# ProtectCircuit.net
KiCad netlist of a schematic drawn in Altium Designer
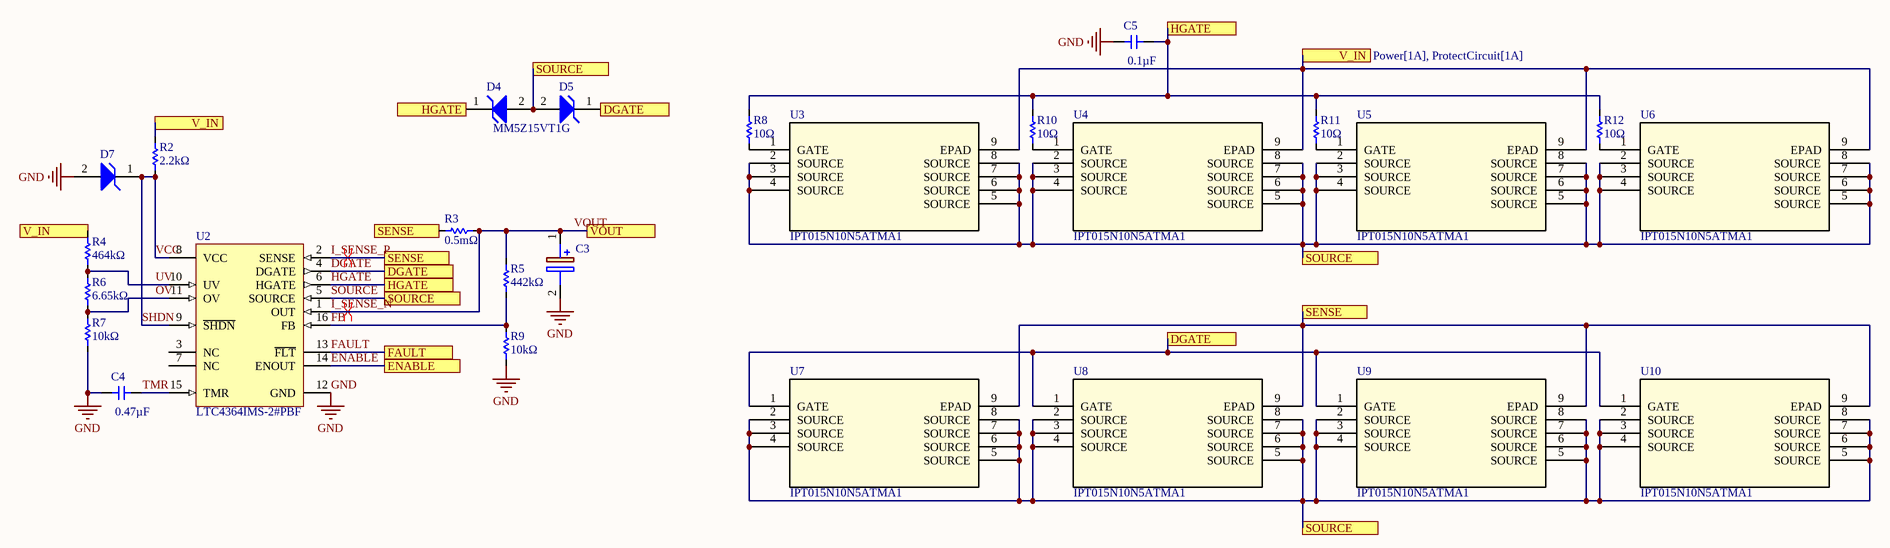
[diagram p0: ProtectCircuit.SchDoc]

(export (version "E")
  (design (tool "Eeschema 10.0.6"))
  (components
    (comp (ref "C3")
      (value "B41858C9477M000")
      (footprint "SamacSys:CAPPRD750W90D1800H3700")
      (description "Capacitor Polarised")
      (fields (field (name "MOUSER PART NUMBER") "871-B41858C9477M"))
      (libsource (lib "*") (part "B41858C9477M000"))
    )
    (comp (ref "C4")
      (value "non-polar_Capacitor")
      (footprint "1210")
      (description "SMD type ceramic capacitor")
      (fields
        (field (name "VOLTAGE") "50V")
        (field (name "CAPACITANCE") "0.47µF")
        (field (name "SOURCE") "robit_passive.SchLib")
      )
      (libsource (lib "robit circuit") (part "Capacitor"))
    )
    (comp (ref "C5")
      (value "non-polar_Capacitor")
      (footprint "1210")
      (description "SMD type ceramic capacitor")
      (fields
        (field (name "VOLTAGE") "50V")
        (field (name "CAPACITANCE") "0.1µF")
        (field (name "SOURCE") "robit_passive.SchLib")
      )
      (libsource (lib "robit circuit") (part "Capacitor"))
    )
    (comp (ref "D4")
      (value "MM5Z15VT1G")
      (footprint "ONSC-SOD-523-2-502-01_V")
      (description "Zener Voltage Regulator, 500 mW, 2-Pin SOD-523, Pb-Free, Tape and Reel")
      (fields (field (name "MANUFACTURER") "On Semiconductor"))
      (libsource (lib "Altium Content Vault") (part "ONSC-K1A2-2"))
    )
    (comp (ref "D5")
      (value "MM5Z15VT1G")
      (footprint "ONSC-SOD-523-2-502-01_V")
      (description "Zener Voltage Regulator, 500 mW, 2-Pin SOD-523, Pb-Free, Tape and Reel")
      (fields (field (name "MANUFACTURER") "On Semiconductor"))
      (libsource (lib "Altium Content Vault") (part "ONSC-K1A2-2"))
    )
    (comp (ref "D7")
      (value "1SMB5945BT3G")
      (footprint "ONSC-SMB-2-403A-03_H_V")
      (description "3 W Zener Voltage Regulator, 2-Pin SMB, Pb-Free, Tape and Reel")
      (fields (field (name "MANUFACTURER") "On Semiconductor"))
      (libsource (lib "Altium Content Vault") (part "ONSC-K1A2-2"))
    )
    (comp (ref "R2") (value "2.2kΩ") (footprint "SMD_2512") (libsource (lib "Resistor") (part "Resistor")))
    (comp (ref "R3") (value "0.5mΩ") (footprint "SMD_2512") (libsource (lib "Resistor") (part "Resistor")))
    (comp (ref "R4") (value "464kΩ") (footprint "SMD_0603") (libsource (lib "Resistor") (part "Resistor")))
    (comp (ref "R5") (value "442kΩ") (footprint "SMD_0603") (libsource (lib "Resistor") (part "Resistor")))
    (comp (ref "R6") (value "6.65kΩ") (footprint "SMD_0603") (libsource (lib "Resistor") (part "Resistor")))
    (comp (ref "R7") (value "10kΩ") (footprint "SMD_0603") (libsource (lib "Resistor") (part "Resistor")))
    (comp (ref "R8") (value "10Ω") (footprint "SMD_0603") (libsource (lib "Resistor") (part "Resistor")))
    (comp (ref "R9") (value "10kΩ") (footprint "SMD_0603") (libsource (lib "Resistor") (part "Resistor")))
    (comp (ref "R10") (value "10Ω") (footprint "SMD_0603") (libsource (lib "Resistor") (part "Resistor")))
    (comp (ref "R11") (value "10Ω") (footprint "SMD_0603") (libsource (lib "Resistor") (part "Resistor")))
    (comp (ref "R12") (value "10Ω") (footprint "SMD_0603") (libsource (lib "Resistor") (part "Resistor")))
    (comp (ref "U2")
      (value "LTC4364IMS-2#PBF")
      (footprint "LT-MS-16_M")
      (description "Surge Stopper with Ideal Diode, 4 to 80 V Vin, 16-pin SOP (MS-16), -40 to 85 degC, Pb-Free")
      (fields (field (name "MANUFACTURER") "Linear Technology"))
      (libsource (lib "Altium Content Vault") (part "LT-LTC4364-S-16"))
    )
    (comp (ref "U3")
      (value "IPT015N10N5ATMA1")
      (footprint "PG-HSOF-8-1_INF")
      (fields (field (name "COPYRIGHT") "Copyright (C) 2025 Ultra Librarian. All rights reserved."))
      (libsource (lib "IPT015N10N5ATMA1") (part "IPT015N10N5ATMA1"))
    )
    (comp (ref "U4")
      (value "IPT015N10N5ATMA1")
      (footprint "PG-HSOF-8-1_INF")
      (fields (field (name "COPYRIGHT") "Copyright (C) 2025 Ultra Librarian. All rights reserved."))
      (libsource (lib "IPT015N10N5ATMA1") (part "IPT015N10N5ATMA1"))
    )
    (comp (ref "U5")
      (value "IPT015N10N5ATMA1")
      (footprint "PG-HSOF-8-1_INF")
      (fields (field (name "COPYRIGHT") "Copyright (C) 2025 Ultra Librarian. All rights reserved."))
      (libsource (lib "IPT015N10N5ATMA1") (part "IPT015N10N5ATMA1"))
    )
    (comp (ref "U6")
      (value "IPT015N10N5ATMA1")
      (footprint "PG-HSOF-8-1_INF")
      (fields (field (name "COPYRIGHT") "Copyright (C) 2025 Ultra Librarian. All rights reserved."))
      (libsource (lib "IPT015N10N5ATMA1") (part "IPT015N10N5ATMA1"))
    )
    (comp (ref "U7")
      (value "IPT015N10N5ATMA1")
      (footprint "PG-HSOF-8-1_INF")
      (fields (field (name "COPYRIGHT") "Copyright (C) 2025 Ultra Librarian. All rights reserved."))
      (libsource (lib "IPT015N10N5ATMA1") (part "IPT015N10N5ATMA1"))
    )
    (comp (ref "U8")
      (value "IPT015N10N5ATMA1")
      (footprint "PG-HSOF-8-1_INF")
      (fields (field (name "COPYRIGHT") "Copyright (C) 2025 Ultra Librarian. All rights reserved."))
      (libsource (lib "IPT015N10N5ATMA1") (part "IPT015N10N5ATMA1"))
    )
    (comp (ref "U9")
      (value "IPT015N10N5ATMA1")
      (footprint "PG-HSOF-8-1_INF")
      (fields (field (name "COPYRIGHT") "Copyright (C) 2025 Ultra Librarian. All rights reserved."))
      (libsource (lib "IPT015N10N5ATMA1") (part "IPT015N10N5ATMA1"))
    )
    (comp (ref "U10")
      (value "IPT015N10N5ATMA1")
      (footprint "PG-HSOF-8-1_INF")
      (fields (field (name "COPYRIGHT") "Copyright (C) 2025 Ultra Librarian. All rights reserved."))
      (libsource (lib "IPT015N10N5ATMA1") (part "IPT015N10N5ATMA1"))
    )
  )
  (nets
    (net (code "1") (name "/DGATE") (class "Default")
      (node (ref "D5") (pin "1") (pinfunction "K_1") (pintype "passive"))
      (node (ref "U10") (pin "1") (pinfunction "GATE_1") (pintype "passive"))
      (node (ref "U2") (pin "4") (pinfunction "DGATE_4") (pintype "output"))
      (node (ref "U7") (pin "1") (pinfunction "GATE_1") (pintype "passive"))
      (node (ref "U8") (pin "1") (pinfunction "GATE_1") (pintype "passive"))
      (node (ref "U9") (pin "1") (pinfunction "GATE_1") (pintype "passive"))
    )
    (net (code "2") (name "/ENABLE") (class "Default")
      (node (ref "U2") (pin "14") (pinfunction "ENOUT_14") (pintype "tri_state"))
    )
    (net (code "3") (name "/FAULT") (class "Default")
      (node (ref "U2") (pin "13") (pinfunction "~{FLT}_13") (pintype "tri_state"))
    )
    (net (code "4") (name "/FB") (class "Default")
      (node (ref "R5") (pin "2") (pinfunction "2_2") (pintype "passive"))
      (node (ref "R9") (pin "1") (pinfunction "1_1") (pintype "passive"))
      (node (ref "U2") (pin "16") (pinfunction "FB_16") (pintype "input"))
    )
    (net (code "5") (name "/HGATE") (class "Default")
      (node (ref "C5") (pin "2") (pinfunction "2_2") (pintype "passive"))
      (node (ref "D4") (pin "1") (pinfunction "K_1") (pintype "passive"))
      (node (ref "R10") (pin "1") (pinfunction "1_1") (pintype "passive"))
      (node (ref "R11") (pin "1") (pinfunction "1_1") (pintype "passive"))
      (node (ref "R12") (pin "1") (pinfunction "1_1") (pintype "passive"))
      (node (ref "R8") (pin "1") (pinfunction "1_1") (pintype "passive"))
      (node (ref "U2") (pin "6") (pinfunction "HGATE_6") (pintype "output"))
    )
    (net (code "6") (name "/I_SENSE_N") (class "Default")
      (node (ref "C3") (pin "1") (pinfunction "+_1") (pintype "passive"))
      (node (ref "R3") (pin "2") (pinfunction "2_2") (pintype "passive"))
      (node (ref "R5") (pin "1") (pinfunction "1_1") (pintype "passive"))
      (node (ref "U2") (pin "1") (pinfunction "OUT_1") (pintype "input"))
    )
    (net (code "7") (name "/I_SENSE_P") (class "Default")
      (node (ref "R3") (pin "1") (pinfunction "1_1") (pintype "passive"))
      (node (ref "U10") (pin "9") (pinfunction "EPAD_9") (pintype "passive"))
      (node (ref "U2") (pin "2") (pinfunction "SENSE_2") (pintype "input"))
      (node (ref "U7") (pin "9") (pinfunction "EPAD_9") (pintype "passive"))
      (node (ref "U8") (pin "9") (pinfunction "EPAD_9") (pintype "passive"))
      (node (ref "U9") (pin "9") (pinfunction "EPAD_9") (pintype "passive"))
    )
    (net (code "8") (name "/OV") (class "Default")
      (node (ref "R6") (pin "2") (pinfunction "2_2") (pintype "passive"))
      (node (ref "R7") (pin "1") (pinfunction "1_1") (pintype "passive"))
      (node (ref "U2") (pin "11") (pinfunction "OV_11") (pintype "input"))
    )
    (net (code "9") (name "/SHDN") (class "Default")
      (node (ref "D7") (pin "1") (pinfunction "K_1") (pintype "passive"))
      (node (ref "R2") (pin "2") (pinfunction "2_2") (pintype "passive"))
      (node (ref "U2") (pin "8") (pinfunction "VCC_8") (pintype "power_in"))
      (node (ref "U2") (pin "9") (pinfunction "~{SHDN}_9") (pintype "input"))
    )
    (net (code "10") (name "/SOURCE") (class "Default")
      (node (ref "D4") (pin "2") (pinfunction "A_2") (pintype "passive"))
      (node (ref "D5") (pin "2") (pinfunction "A_2") (pintype "passive"))
      (node (ref "U10") (pin "2") (pinfunction "SOURCE_2") (pintype "passive"))
      (node (ref "U10") (pin "3") (pinfunction "SOURCE_3") (pintype "passive"))
      (node (ref "U10") (pin "4") (pinfunction "SOURCE_4") (pintype "passive"))
      (node (ref "U10") (pin "5") (pinfunction "SOURCE_5") (pintype "passive"))
      (node (ref "U10") (pin "6") (pinfunction "SOURCE_6") (pintype "passive"))
      (node (ref "U10") (pin "7") (pinfunction "SOURCE_7") (pintype "passive"))
      (node (ref "U10") (pin "8") (pinfunction "SOURCE_8") (pintype "passive"))
      (node (ref "U2") (pin "5") (pinfunction "SOURCE_5") (pintype "input"))
      (node (ref "U3") (pin "2") (pinfunction "SOURCE_2") (pintype "passive"))
      (node (ref "U3") (pin "3") (pinfunction "SOURCE_3") (pintype "passive"))
      (node (ref "U3") (pin "4") (pinfunction "SOURCE_4") (pintype "passive"))
      (node (ref "U3") (pin "5") (pinfunction "SOURCE_5") (pintype "passive"))
      (node (ref "U3") (pin "6") (pinfunction "SOURCE_6") (pintype "passive"))
      (node (ref "U3") (pin "7") (pinfunction "SOURCE_7") (pintype "passive"))
      (node (ref "U3") (pin "8") (pinfunction "SOURCE_8") (pintype "passive"))
      (node (ref "U4") (pin "2") (pinfunction "SOURCE_2") (pintype "passive"))
      (node (ref "U4") (pin "3") (pinfunction "SOURCE_3") (pintype "passive"))
      (node (ref "U4") (pin "4") (pinfunction "SOURCE_4") (pintype "passive"))
      (node (ref "U4") (pin "5") (pinfunction "SOURCE_5") (pintype "passive"))
      (node (ref "U4") (pin "6") (pinfunction "SOURCE_6") (pintype "passive"))
      (node (ref "U4") (pin "7") (pinfunction "SOURCE_7") (pintype "passive"))
      (node (ref "U4") (pin "8") (pinfunction "SOURCE_8") (pintype "passive"))
      (node (ref "U5") (pin "2") (pinfunction "SOURCE_2") (pintype "passive"))
      (node (ref "U5") (pin "3") (pinfunction "SOURCE_3") (pintype "passive"))
      (node (ref "U5") (pin "4") (pinfunction "SOURCE_4") (pintype "passive"))
      (node (ref "U5") (pin "5") (pinfunction "SOURCE_5") (pintype "passive"))
      (node (ref "U5") (pin "6") (pinfunction "SOURCE_6") (pintype "passive"))
      (node (ref "U5") (pin "7") (pinfunction "SOURCE_7") (pintype "passive"))
      (node (ref "U5") (pin "8") (pinfunction "SOURCE_8") (pintype "passive"))
      (node (ref "U6") (pin "2") (pinfunction "SOURCE_2") (pintype "passive"))
      (node (ref "U6") (pin "3") (pinfunction "SOURCE_3") (pintype "passive"))
      (node (ref "U6") (pin "4") (pinfunction "SOURCE_4") (pintype "passive"))
      (node (ref "U6") (pin "5") (pinfunction "SOURCE_5") (pintype "passive"))
      (node (ref "U6") (pin "6") (pinfunction "SOURCE_6") (pintype "passive"))
      (node (ref "U6") (pin "7") (pinfunction "SOURCE_7") (pintype "passive"))
      (node (ref "U6") (pin "8") (pinfunction "SOURCE_8") (pintype "passive"))
      (node (ref "U7") (pin "2") (pinfunction "SOURCE_2") (pintype "passive"))
      (node (ref "U7") (pin "3") (pinfunction "SOURCE_3") (pintype "passive"))
      (node (ref "U7") (pin "4") (pinfunction "SOURCE_4") (pintype "passive"))
      (node (ref "U7") (pin "5") (pinfunction "SOURCE_5") (pintype "passive"))
      (node (ref "U7") (pin "6") (pinfunction "SOURCE_6") (pintype "passive"))
      (node (ref "U7") (pin "7") (pinfunction "SOURCE_7") (pintype "passive"))
      (node (ref "U7") (pin "8") (pinfunction "SOURCE_8") (pintype "passive"))
      (node (ref "U8") (pin "2") (pinfunction "SOURCE_2") (pintype "passive"))
      (node (ref "U8") (pin "3") (pinfunction "SOURCE_3") (pintype "passive"))
      (node (ref "U8") (pin "4") (pinfunction "SOURCE_4") (pintype "passive"))
      (node (ref "U8") (pin "5") (pinfunction "SOURCE_5") (pintype "passive"))
      (node (ref "U8") (pin "6") (pinfunction "SOURCE_6") (pintype "passive"))
      (node (ref "U8") (pin "7") (pinfunction "SOURCE_7") (pintype "passive"))
      (node (ref "U8") (pin "8") (pinfunction "SOURCE_8") (pintype "passive"))
      (node (ref "U9") (pin "2") (pinfunction "SOURCE_2") (pintype "passive"))
      (node (ref "U9") (pin "3") (pinfunction "SOURCE_3") (pintype "passive"))
      (node (ref "U9") (pin "4") (pinfunction "SOURCE_4") (pintype "passive"))
      (node (ref "U9") (pin "5") (pinfunction "SOURCE_5") (pintype "passive"))
      (node (ref "U9") (pin "6") (pinfunction "SOURCE_6") (pintype "passive"))
      (node (ref "U9") (pin "7") (pinfunction "SOURCE_7") (pintype "passive"))
      (node (ref "U9") (pin "8") (pinfunction "SOURCE_8") (pintype "passive"))
    )
    (net (code "11") (name "/TMR") (class "Default")
      (node (ref "C4") (pin "2") (pinfunction "2_2") (pintype "passive"))
      (node (ref "U2") (pin "15") (pinfunction "TMR_15") (pintype "input"))
    )
    (net (code "12") (name "/UV") (class "Default")
      (node (ref "R4") (pin "2") (pinfunction "2_2") (pintype "passive"))
      (node (ref "R6") (pin "1") (pinfunction "1_1") (pintype "passive"))
      (node (ref "U2") (pin "10") (pinfunction "UV_10") (pintype "input"))
    )
    (net (code "13") (name "/V_IN") (class "Default")
      (node (ref "R2") (pin "1") (pinfunction "1_1") (pintype "passive"))
      (node (ref "R4") (pin "1") (pinfunction "1_1") (pintype "passive"))
      (node (ref "U3") (pin "9") (pinfunction "EPAD_9") (pintype "passive"))
      (node (ref "U4") (pin "9") (pinfunction "EPAD_9") (pintype "passive"))
      (node (ref "U5") (pin "9") (pinfunction "EPAD_9") (pintype "passive"))
      (node (ref "U6") (pin "9") (pinfunction "EPAD_9") (pintype "passive"))
    )
    (net (code "14") (name "GND") (class "Default")
      (node (ref "C3") (pin "2") (pinfunction "-_2") (pintype "passive"))
      (node (ref "C4") (pin "1") (pinfunction "1_1") (pintype "passive"))
      (node (ref "C5") (pin "1") (pinfunction "1_1") (pintype "passive"))
      (node (ref "D7") (pin "2") (pinfunction "A_2") (pintype "passive"))
      (node (ref "R7") (pin "2") (pinfunction "2_2") (pintype "passive"))
      (node (ref "R9") (pin "2") (pinfunction "2_2") (pintype "passive"))
      (node (ref "U2") (pin "12") (pinfunction "GND_12") (pintype "power_in"))
    )
    (net (code "15") (name "Net-(U3-GATE)") (class "Default")
      (node (ref "R8") (pin "2") (pinfunction "2_2") (pintype "passive"))
      (node (ref "U3") (pin "1") (pinfunction "GATE_1") (pintype "passive"))
    )
    (net (code "16") (name "Net-(U4-GATE)") (class "Default")
      (node (ref "R10") (pin "2") (pinfunction "2_2") (pintype "passive"))
      (node (ref "U4") (pin "1") (pinfunction "GATE_1") (pintype "passive"))
    )
    (net (code "17") (name "Net-(U5-GATE)") (class "Default")
      (node (ref "R11") (pin "2") (pinfunction "2_2") (pintype "passive"))
      (node (ref "U5") (pin "1") (pinfunction "GATE_1") (pintype "passive"))
    )
    (net (code "18") (name "Net-(U6-GATE)") (class "Default")
      (node (ref "R12") (pin "2") (pinfunction "2_2") (pintype "passive"))
      (node (ref "U6") (pin "1") (pinfunction "GATE_1") (pintype "passive"))
    )
    (net (code "19") (name "unconnected-(U2-NC-Pad3)") (class "Default")
      (node (ref "U2") (pin "3") (pinfunction "NC_3") (pintype "passive"))
    )
    (net (code "20") (name "unconnected-(U2-NC-Pad7)") (class "Default")
      (node (ref "U2") (pin "7") (pinfunction "NC_7") (pintype "passive"))
    )
  )
)
